# pots.net
KiCad netlist of a schematic drawn in EAGLE
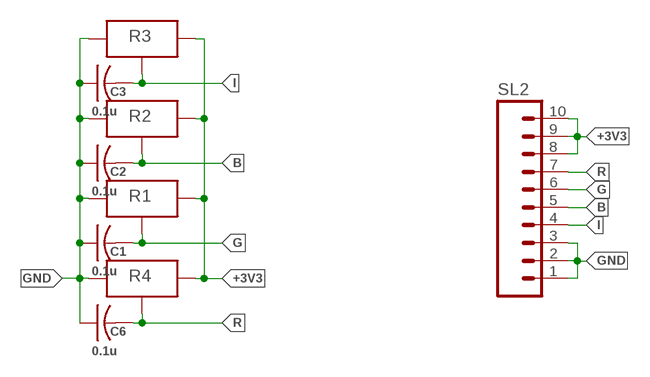
[diagram p0: schematic, sheet 1]

(export (version "E")
  (design (tool "Eeschema 10.0.6"))
  (components
    (comp (ref "C1")
      (value "0.1u")
      (footprint "eagle-import:C0603")
      (libsource (lib "eagle-import") (part "CAP0603"))
    )
    (comp (ref "C2")
      (value "0.1u")
      (footprint "eagle-import:C0603")
      (libsource (lib "eagle-import") (part "CAP0603"))
    )
    (comp (ref "C3")
      (value "0.1u")
      (footprint "eagle-import:C0603")
      (libsource (lib "eagle-import") (part "CAP0603"))
    )
    (comp (ref "C6")
      (value "0.1u")
      (footprint "eagle-import:C0603")
      (libsource (lib "eagle-import") (part "CAP0603"))
    )
    (comp (ref "R1")
      (value "POTNORMAL")
      (footprint "eagle-import:RJ9W")
      (libsource (lib "eagle-import") (part "POTNORMAL"))
    )
    (comp (ref "R2")
      (value "POTNORMAL")
      (footprint "eagle-import:RJ9W")
      (libsource (lib "eagle-import") (part "POTNORMAL"))
    )
    (comp (ref "R3")
      (value "POTNORMAL")
      (footprint "eagle-import:RJ9W")
      (libsource (lib "eagle-import") (part "POTNORMAL"))
    )
    (comp (ref "R4")
      (value "POTNORMAL")
      (footprint "eagle-import:RJ9W")
      (libsource (lib "eagle-import") (part "POTNORMAL"))
    )
    (comp (ref "SL2")
      (value "M10")
      (footprint "eagle-import:10P")
      (libsource (lib "eagle-import") (part "M10"))
    )
  )
  (nets
    (net (code "1") (name "+3V3") (class "Default")
      (node (ref "R1") (pin "A") (pinfunction "A_A") (pintype "passive"))
      (node (ref "R2") (pin "A") (pinfunction "A_A") (pintype "passive"))
      (node (ref "R3") (pin "A") (pinfunction "A_A") (pintype "passive"))
      (node (ref "R4") (pin "A") (pinfunction "A_A") (pintype "passive"))
      (node (ref "SL2") (pin "10") (pinfunction "10_10") (pintype "passive"))
      (node (ref "SL2") (pin "8") (pinfunction "8_8") (pintype "passive"))
      (node (ref "SL2") (pin "9") (pinfunction "9_9") (pintype "passive"))
    )
    (net (code "2") (name "B") (class "Default")
      (node (ref "C2") (pin "2") (pinfunction "2_2") (pintype "passive"))
      (node (ref "R2") (pin "S") (pinfunction "S_S") (pintype "passive"))
      (node (ref "SL2") (pin "5") (pinfunction "5_5") (pintype "passive"))
    )
    (net (code "3") (name "G") (class "Default")
      (node (ref "C1") (pin "2") (pinfunction "2_2") (pintype "passive"))
      (node (ref "R1") (pin "S") (pinfunction "S_S") (pintype "passive"))
      (node (ref "SL2") (pin "6") (pinfunction "6_6") (pintype "passive"))
    )
    (net (code "4") (name "GND") (class "Default")
      (node (ref "C1") (pin "1") (pinfunction "1_1") (pintype "passive"))
      (node (ref "C2") (pin "1") (pinfunction "1_1") (pintype "passive"))
      (node (ref "C3") (pin "1") (pinfunction "1_1") (pintype "passive"))
      (node (ref "C6") (pin "1") (pinfunction "1_1") (pintype "passive"))
      (node (ref "R1") (pin "E") (pinfunction "E_E") (pintype "passive"))
      (node (ref "R2") (pin "E") (pinfunction "E_E") (pintype "passive"))
      (node (ref "R3") (pin "E") (pinfunction "E_E") (pintype "passive"))
      (node (ref "R4") (pin "E") (pinfunction "E_E") (pintype "passive"))
      (node (ref "SL2") (pin "1") (pinfunction "1_1") (pintype "passive"))
      (node (ref "SL2") (pin "2") (pinfunction "2_2") (pintype "passive"))
      (node (ref "SL2") (pin "3") (pinfunction "3_3") (pintype "passive"))
    )
    (net (code "5") (name "I") (class "Default")
      (node (ref "C3") (pin "2") (pinfunction "2_2") (pintype "passive"))
      (node (ref "R3") (pin "S") (pinfunction "S_S") (pintype "passive"))
      (node (ref "SL2") (pin "4") (pinfunction "4_4") (pintype "passive"))
    )
    (net (code "6") (name "R") (class "Default")
      (node (ref "C6") (pin "2") (pinfunction "2_2") (pintype "passive"))
      (node (ref "R4") (pin "S") (pinfunction "S_S") (pintype "passive"))
      (node (ref "SL2") (pin "7") (pinfunction "7_7") (pintype "passive"))
    )
  )
)
